# BMS_1_2026-08-27.net
KiCad netlist of a schematic drawn in Altium Designer
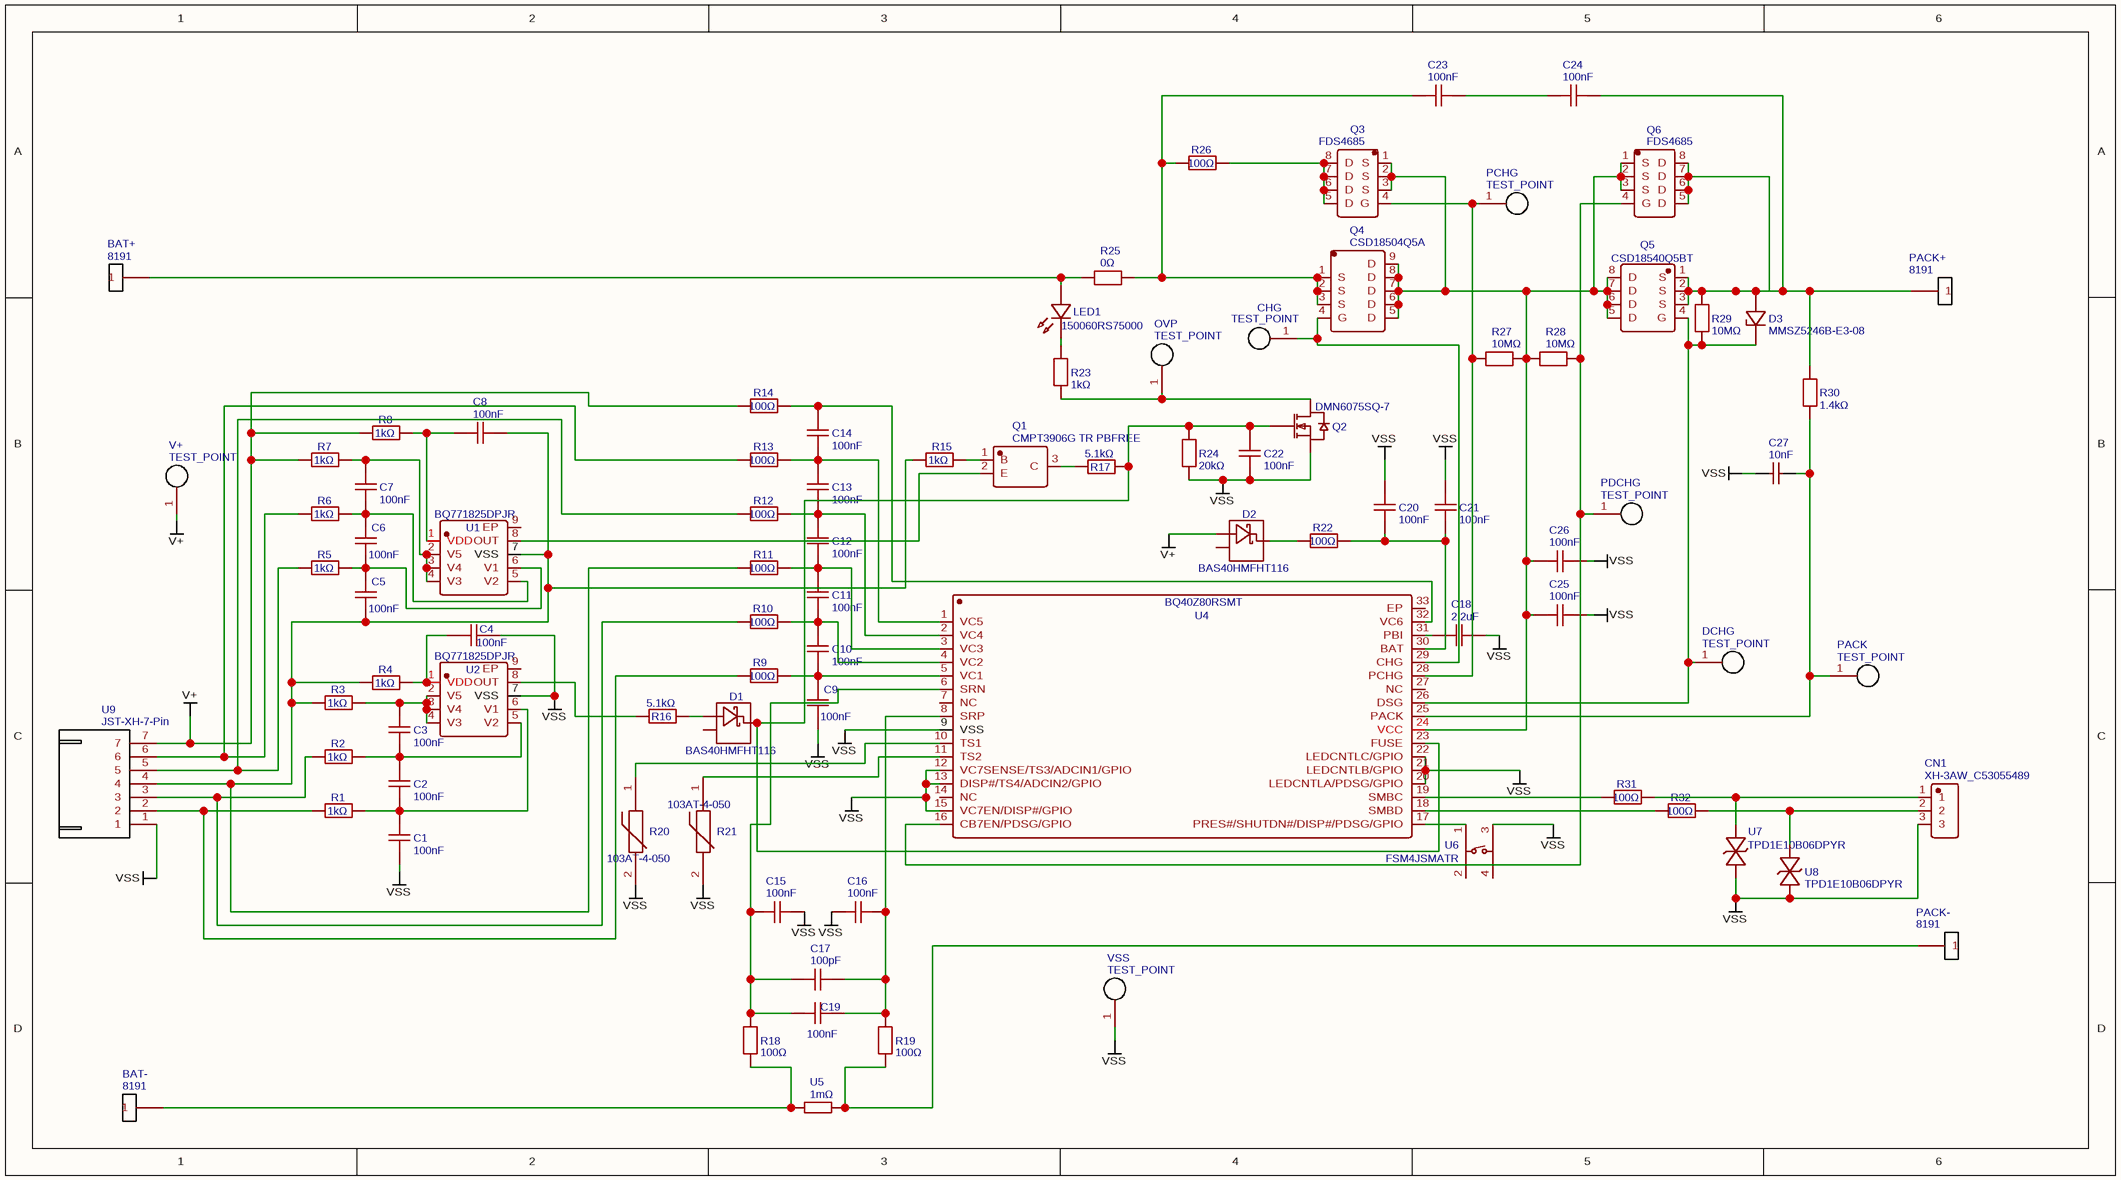
[diagram p0: BMS_1_2026-08-27.schdoc]

(export (version "E")
  (design (tool "Eeschema 10.0.6"))
  (components
    (comp (ref "BAT+")
      (value "8191")
      (fields (field (name "CONTRIBUTOR") "carlo1300"))
      (libsource (lib "altium-import") (part "root_0_8191_"))
    )
    (comp (ref "BAT-")
      (value "8191")
      (fields (field (name "CONTRIBUTOR") "carlo1300"))
      (libsource (lib "altium-import") (part "root_0_8191_"))
    )
    (comp (ref "C1")
      (value "100nF")
      (fields
        (field (name "MANUFACTURER") "muRata(村田)")
        (field (name "MANUFACTURER PART") "GRM188R71H104KA93D")
      )
      (libsource (lib "altium-import") (part "root_1_100nF_"))
    )
    (comp (ref "C2")
      (value "100nF")
      (fields
        (field (name "MANUFACTURER") "muRata(村田)")
        (field (name "MANUFACTURER PART") "GRM188R71H104KA93D")
      )
      (libsource (lib "altium-import") (part "root_1_100nF_"))
    )
    (comp (ref "C3")
      (value "100nF")
      (fields
        (field (name "MANUFACTURER") "muRata(村田)")
        (field (name "MANUFACTURER PART") "GRM188R71H104KA93D")
      )
      (libsource (lib "altium-import") (part "root_1_100nF_"))
    )
    (comp (ref "C4")
      (value "100nF")
      (fields
        (field (name "MANUFACTURER") "muRata(村田)")
        (field (name "MANUFACTURER PART") "GRM188R71H104KA93D")
      )
      (libsource (lib "altium-import") (part "root_2_100nF_"))
    )
    (comp (ref "C5")
      (value "100nF")
      (fields
        (field (name "MANUFACTURER") "muRata(村田)")
        (field (name "MANUFACTURER PART") "GRM188R71H104KA93D")
      )
      (libsource (lib "altium-import") (part "root_1_100nF_"))
    )
    (comp (ref "C6")
      (value "100nF")
      (fields
        (field (name "MANUFACTURER") "muRata(村田)")
        (field (name "MANUFACTURER PART") "GRM188R71H104KA93D")
      )
      (libsource (lib "altium-import") (part "root_1_100nF_"))
    )
    (comp (ref "C7")
      (value "100nF")
      (fields
        (field (name "MANUFACTURER") "muRata(村田)")
        (field (name "MANUFACTURER PART") "GRM188R71H104KA93D")
      )
      (libsource (lib "altium-import") (part "root_1_100nF_"))
    )
    (comp (ref "C8")
      (value "100nF")
      (fields
        (field (name "MANUFACTURER") "muRata(村田)")
        (field (name "MANUFACTURER PART") "GRM188R71H104KA93D")
      )
      (libsource (lib "altium-import") (part "root_2_100nF_"))
    )
    (comp (ref "C9")
      (value "100nF")
      (fields
        (field (name "MANUFACTURER") "muRata(村田)")
        (field (name "MANUFACTURER PART") "GRM188R71H104KA93D")
      )
      (libsource (lib "altium-import") (part "root_1_100nF_"))
    )
    (comp (ref "C10")
      (value "100nF")
      (fields
        (field (name "MANUFACTURER") "muRata(村田)")
        (field (name "MANUFACTURER PART") "GRM188R71H104KA93D")
      )
      (libsource (lib "altium-import") (part "root_1_100nF_"))
    )
    (comp (ref "C11")
      (value "100nF")
      (fields
        (field (name "MANUFACTURER") "muRata(村田)")
        (field (name "MANUFACTURER PART") "GRM188R71H104KA93D")
      )
      (libsource (lib "altium-import") (part "root_1_100nF_"))
    )
    (comp (ref "C12")
      (value "100nF")
      (fields
        (field (name "MANUFACTURER") "muRata(村田)")
        (field (name "MANUFACTURER PART") "GRM188R71H104KA93D")
      )
      (libsource (lib "altium-import") (part "root_1_100nF_"))
    )
    (comp (ref "C13")
      (value "100nF")
      (fields
        (field (name "MANUFACTURER") "muRata(村田)")
        (field (name "MANUFACTURER PART") "GRM188R71H104KA93D")
      )
      (libsource (lib "altium-import") (part "root_1_100nF_"))
    )
    (comp (ref "C14")
      (value "100nF")
      (fields
        (field (name "MANUFACTURER") "muRata(村田)")
        (field (name "MANUFACTURER PART") "GRM188R71H104KA93D")
      )
      (libsource (lib "altium-import") (part "root_1_100nF_"))
    )
    (comp (ref "C15")
      (value "100nF")
      (fields
        (field (name "MANUFACTURER") "muRata(村田)")
        (field (name "MANUFACTURER PART") "GRM188R71H104KA93D")
      )
      (libsource (lib "altium-import") (part "root_0_100nF_"))
    )
    (comp (ref "C16")
      (value "100nF")
      (fields
        (field (name "MANUFACTURER") "muRata(村田)")
        (field (name "MANUFACTURER PART") "GRM188R71H104KA93D")
      )
      (libsource (lib "altium-import") (part "root_2_100nF_"))
    )
    (comp (ref "C17")
      (value "100pF")
      (fields
        (field (name "MANUFACTURER") "KEMET(基美)")
        (field (name "MANUFACTURER PART") "C0603C101J5GAC3121")
        (field (name "CONTRIBUTOR") "LCSC")
      )
      (libsource (lib "altium-import") (part "root_0_100pF_"))
    )
    (comp (ref "C18")
      (value "2.2uF")
      (fields
        (field (name "MANUFACTURER") "muRata(村田)")
        (field (name "MANUFACTURER PART") "GRM21BR71E225KA73L")
        (field (name "CONTRIBUTOR") "LCSC")
      )
      (libsource (lib "altium-import") (part "root_0_2.2uF_"))
    )
    (comp (ref "C19")
      (value "100nF")
      (fields
        (field (name "MANUFACTURER") "muRata(村田)")
        (field (name "MANUFACTURER PART") "GRM188R71H104KA93D")
      )
      (libsource (lib "altium-import") (part "root_2_100nF_"))
    )
    (comp (ref "C20")
      (value "100nF")
      (fields
        (field (name "MANUFACTURER") "muRata(村田)")
        (field (name "MANUFACTURER PART") "GRM188R71H104KA93D")
      )
      (libsource (lib "altium-import") (part "root_1_100nF_"))
    )
    (comp (ref "C21")
      (value "100nF")
      (fields
        (field (name "MANUFACTURER") "muRata(村田)")
        (field (name "MANUFACTURER PART") "GRM188R71H104KA93D")
      )
      (libsource (lib "altium-import") (part "root_1_100nF_"))
    )
    (comp (ref "C22")
      (value "100nF")
      (fields
        (field (name "MANUFACTURER") "muRata(村田)")
        (field (name "MANUFACTURER PART") "GRM188R71H104KA93D")
      )
      (libsource (lib "altium-import") (part "root_1_100nF_"))
    )
    (comp (ref "C23")
      (value "100nF")
      (fields
        (field (name "MANUFACTURER") "muRata(村田)")
        (field (name "MANUFACTURER PART") "GRM188R71H104KA93D")
      )
      (libsource (lib "altium-import") (part "root_2_100nF_"))
    )
    (comp (ref "C24")
      (value "100nF")
      (fields
        (field (name "MANUFACTURER") "muRata(村田)")
        (field (name "MANUFACTURER PART") "GRM188R71H104KA93D")
      )
      (libsource (lib "altium-import") (part "root_2_100nF_"))
    )
    (comp (ref "C25")
      (value "100nF")
      (fields
        (field (name "MANUFACTURER") "muRata(村田)")
        (field (name "MANUFACTURER PART") "GRM188R71H104KA93D")
      )
      (libsource (lib "altium-import") (part "root_2_100nF_"))
    )
    (comp (ref "C26")
      (value "100nF")
      (fields
        (field (name "MANUFACTURER") "muRata(村田)")
        (field (name "MANUFACTURER PART") "GRM188R71H104KA93D")
      )
      (libsource (lib "altium-import") (part "root_2_100nF_"))
    )
    (comp (ref "C27")
      (value "10nF")
      (fields
        (field (name "MANUFACTURER PART") "GRM188R71H103KA01D")
        (field (name "MANUFACTURER") "muRata(村田)")
      )
      (libsource (lib "altium-import") (part "root_0_10nF_"))
    )
    (comp (ref "CHG")
      (value "TEST_POINT")
      (fields (field (name "CONTRIBUTOR") "erandi"))
      (libsource (lib "altium-import") (part "root_0_TEST_POINT_"))
    )
    (comp (ref "CN1")
      (value "XH-3AW_C53055489")
      (fields
        (field (name "MANUFACTURER") "LXWCONN(连兴旺电子)")
        (field (name "MANUFACTURER PART") "XH-3AW")
        (field (name "CONTRIBUTOR") "lcsc")
      )
      (libsource (lib "altium-import") (part "root_0_XH-3AW_C53055489_"))
    )
    (comp (ref "D1")
      (value "BAS40HMFHT116")
      (fields (field (name "MANUFACTURER") "ROHM(罗姆)") (field (name "CONTRIBUTOR") "LCSC"))
      (libsource (lib "altium-import") (part "root_3_BAS40HMFHT116_"))
    )
    (comp (ref "D2")
      (value "BAS40HMFHT116")
      (fields (field (name "MANUFACTURER") "ROHM(罗姆)") (field (name "CONTRIBUTOR") "LCSC"))
      (libsource (lib "altium-import") (part "root_3_BAS40HMFHT116_"))
    )
    (comp (ref "D3")
      (value "MMSZ5246B-E3-08")
      (fields (field (name "MANUFACTURER") "VISHAY(威世)") (field (name "CONTRIBUTOR") "lcsc"))
      (libsource (lib "altium-import") (part "root_3_MMSZ5246B-E3-08_"))
    )
    (comp (ref "DCHG")
      (value "TEST_POINT")
      (fields (field (name "CONTRIBUTOR") "erandi"))
      (libsource (lib "altium-import") (part "root_2_TEST_POINT_"))
    )
    (comp (ref "LED1")
      (value "150060RS75000")
      (fields (field (name "MANUFACTURER") "Wurth(伍尔特)") (field (name "CONTRIBUTOR") "lcsc"))
      (libsource (lib "altium-import") (part "root_1_150060RS75000_"))
    )
    (comp (ref "OVP")
      (value "TEST_POINT")
      (fields (field (name "CONTRIBUTOR") "erandi"))
      (libsource (lib "altium-import") (part "root_3_TEST_POINT_"))
    )
    (comp (ref "PACK")
      (value "TEST_POINT")
      (fields (field (name "CONTRIBUTOR") "erandi"))
      (libsource (lib "altium-import") (part "root_2_TEST_POINT_"))
    )
    (comp (ref "PACK+")
      (value "8191")
      (fields (field (name "CONTRIBUTOR") "carlo1300"))
      (libsource (lib "altium-import") (part "root_2_8191_"))
    )
    (comp (ref "PACK-")
      (value "8191")
      (fields (field (name "CONTRIBUTOR") "carlo1300"))
      (libsource (lib "altium-import") (part "root_2_8191_"))
    )
    (comp (ref "PCHG")
      (value "TEST_POINT")
      (fields (field (name "CONTRIBUTOR") "erandi"))
      (libsource (lib "altium-import") (part "root_2_TEST_POINT_"))
    )
    (comp (ref "PDCHG")
      (value "TEST_POINT")
      (fields (field (name "CONTRIBUTOR") "erandi"))
      (libsource (lib "altium-import") (part "root_2_TEST_POINT_"))
    )
    (comp (ref "Q1")
      (value "CMPT3906G TR PBFREE")
      (fields (field (name "MANUFACTURER") "Central(中环)") (field (name "CONTRIBUTOR") "lcsc"))
      (libsource (lib "altium-import") (part "root_0_CMPT3906G TR PBFREE_"))
    )
    (comp (ref "Q2")
      (value "DMN6075SQ-7")
      (fields (field (name "MANUFACTURER") "DIODES(美台)") (field (name "CONTRIBUTOR") "lcsc"))
      (libsource (lib "altium-import") (part "root_0_DMN6075SQ-7_"))
    )
    (comp (ref "Q3")
      (value "FDS4685")
      (fields (field (name "MANUFACTURER") "onsemi(安森美)") (field (name "CONTRIBUTOR") "LCSC"))
      (libsource (lib "") (part "root_0_FDS4685__1"))
    )
    (comp (ref "Q4")
      (value "CSD18504Q5A")
      (fields (field (name "MANUFACTURER") "TI(德州仪器)") (field (name "CONTRIBUTOR") "LCSC"))
      (libsource (lib "altium-import") (part "root_0_CSD18504Q5A_"))
    )
    (comp (ref "Q5")
      (value "CSD18540Q5BT")
      (fields (field (name "MANUFACTURER") "TI(德州仪器)") (field (name "CONTRIBUTOR") "LCSC"))
      (libsource (lib "altium-import") (part "root_0_CSD18540Q5BT_"))
    )
    (comp (ref "Q6")
      (value "FDS4685")
      (fields (field (name "MANUFACTURER") "onsemi(安森美)") (field (name "CONTRIBUTOR") "LCSC"))
      (libsource (lib "altium-import") (part "root_0_FDS4685_"))
    )
    (comp (ref "R1")
      (value "1kΩ")
      (fields
        (field (name "MANUFACTURER") "VISHAY(威世)")
        (field (name "MANUFACTURER PART") "CRCW06031K00JNEA")
        (field (name "CONTRIBUTOR") "LCSC")
      )
      (libsource (lib "altium-import") (part "root_0_1kΩ_"))
    )
    (comp (ref "R2")
      (value "1kΩ")
      (fields
        (field (name "MANUFACTURER") "VISHAY(威世)")
        (field (name "MANUFACTURER PART") "CRCW06031K00JNEA")
        (field (name "CONTRIBUTOR") "LCSC")
      )
      (libsource (lib "altium-import") (part "root_0_1kΩ_"))
    )
    (comp (ref "R3")
      (value "1kΩ")
      (fields
        (field (name "MANUFACTURER") "VISHAY(威世)")
        (field (name "MANUFACTURER PART") "CRCW06031K00JNEA")
        (field (name "CONTRIBUTOR") "LCSC")
      )
      (libsource (lib "altium-import") (part "root_0_1kΩ_"))
    )
    (comp (ref "R4")
      (value "1kΩ")
      (fields
        (field (name "MANUFACTURER") "VISHAY(威世)")
        (field (name "MANUFACTURER PART") "CRCW06031K00JNEA")
        (field (name "CONTRIBUTOR") "LCSC")
      )
      (libsource (lib "altium-import") (part "root_0_1kΩ_"))
    )
    (comp (ref "R5")
      (value "1kΩ")
      (fields
        (field (name "MANUFACTURER") "VISHAY(威世)")
        (field (name "MANUFACTURER PART") "CRCW06031K00JNEA")
        (field (name "CONTRIBUTOR") "LCSC")
      )
      (libsource (lib "altium-import") (part "root_0_1kΩ_"))
    )
    (comp (ref "R6")
      (value "1kΩ")
      (fields
        (field (name "MANUFACTURER") "VISHAY(威世)")
        (field (name "MANUFACTURER PART") "CRCW06031K00JNEA")
        (field (name "CONTRIBUTOR") "LCSC")
      )
      (libsource (lib "altium-import") (part "root_0_1kΩ_"))
    )
    (comp (ref "R7")
      (value "1kΩ")
      (fields
        (field (name "MANUFACTURER") "VISHAY(威世)")
        (field (name "MANUFACTURER PART") "CRCW06031K00JNEA")
        (field (name "CONTRIBUTOR") "LCSC")
      )
      (libsource (lib "altium-import") (part "root_0_1kΩ_"))
    )
    (comp (ref "R8")
      (value "1kΩ")
      (fields
        (field (name "MANUFACTURER") "VISHAY(威世)")
        (field (name "MANUFACTURER PART") "CRCW06031K00JNEA")
        (field (name "CONTRIBUTOR") "LCSC")
      )
      (libsource (lib "altium-import") (part "root_0_1kΩ_"))
    )
    (comp (ref "R9")
      (value "100Ω")
      (fields
        (field (name "MANUFACTURER") "VISHAY(威世)")
        (field (name "MANUFACTURER PART") "CRCW0603100RJNEA")
        (field (name "CONTRIBUTOR") "LCSC")
      )
      (libsource (lib "altium-import") (part "root_0_100Ω_"))
    )
    (comp (ref "R10")
      (value "100Ω")
      (fields
        (field (name "MANUFACTURER") "VISHAY(威世)")
        (field (name "MANUFACTURER PART") "CRCW0603100RJNEA")
        (field (name "CONTRIBUTOR") "LCSC")
      )
      (libsource (lib "altium-import") (part "root_0_100Ω_"))
    )
    (comp (ref "R11")
      (value "100Ω")
      (fields
        (field (name "MANUFACTURER") "VISHAY(威世)")
        (field (name "MANUFACTURER PART") "CRCW0603100RJNEA")
        (field (name "CONTRIBUTOR") "LCSC")
      )
      (libsource (lib "altium-import") (part "root_0_100Ω_"))
    )
    (comp (ref "R12")
      (value "100Ω")
      (fields
        (field (name "MANUFACTURER") "VISHAY(威世)")
        (field (name "MANUFACTURER PART") "CRCW0603100RJNEA")
        (field (name "CONTRIBUTOR") "LCSC")
      )
      (libsource (lib "altium-import") (part "root_0_100Ω_"))
    )
    (comp (ref "R13")
      (value "100Ω")
      (fields
        (field (name "MANUFACTURER") "VISHAY(威世)")
        (field (name "MANUFACTURER PART") "CRCW0603100RJNEA")
        (field (name "CONTRIBUTOR") "LCSC")
      )
      (libsource (lib "altium-import") (part "root_0_100Ω_"))
    )
    (comp (ref "R14")
      (value "100Ω")
      (fields
        (field (name "MANUFACTURER") "VISHAY(威世)")
        (field (name "MANUFACTURER PART") "CRCW0603100RJNEA")
        (field (name "CONTRIBUTOR") "LCSC")
      )
      (libsource (lib "altium-import") (part "root_0_100Ω_"))
    )
    (comp (ref "R15")
      (value "1kΩ")
      (fields
        (field (name "MANUFACTURER") "VISHAY(威世)")
        (field (name "MANUFACTURER PART") "CRCW06031K00JNEA")
        (field (name "CONTRIBUTOR") "LCSC")
      )
      (libsource (lib "altium-import") (part "root_0_1kΩ_"))
    )
    (comp (ref "R16")
      (value "5.1kΩ")
      (fields
        (field (name "MANUFACTURER") "VISHAY(威世)")
        (field (name "MANUFACTURER PART") "CRCW06035K10JNEA")
        (field (name "CONTRIBUTOR") "LCSC")
      )
      (libsource (lib "altium-import") (part "root_0_5.1kΩ_"))
    )
    (comp (ref "R17")
      (value "5.1kΩ")
      (fields
        (field (name "MANUFACTURER") "VISHAY(威世)")
        (field (name "MANUFACTURER PART") "CRCW06035K10JNEA")
        (field (name "CONTRIBUTOR") "LCSC")
      )
      (libsource (lib "altium-import") (part "root_0_5.1kΩ_"))
    )
    (comp (ref "R18")
      (value "100Ω")
      (fields
        (field (name "MANUFACTURER") "VISHAY(威世)")
        (field (name "MANUFACTURER PART") "CRCW0603100RJNEA")
        (field (name "CONTRIBUTOR") "LCSC")
      )
      (libsource (lib "altium-import") (part "root_3_100Ω_"))
    )
    (comp (ref "R19")
      (value "100Ω")
      (fields
        (field (name "MANUFACTURER") "VISHAY(威世)")
        (field (name "MANUFACTURER PART") "CRCW0603100RJNEA")
        (field (name "CONTRIBUTOR") "LCSC")
      )
      (libsource (lib "altium-import") (part "root_1_100Ω_"))
    )
    (comp (ref "R20")
      (value "103AT-4-050")
      (fields (field (name "MANUFACTURER") "semitec(石冢)") (field (name "CONTRIBUTOR") "LCSC"))
      (libsource (lib "altium-import") (part "root_3_103AT-4-050_"))
    )
    (comp (ref "R21")
      (value "103AT-4-050")
      (fields (field (name "MANUFACTURER") "semitec(石冢)") (field (name "CONTRIBUTOR") "LCSC"))
      (libsource (lib "altium-import") (part "root_3_103AT-4-050_"))
    )
    (comp (ref "R22")
      (value "100Ω")
      (fields
        (field (name "MANUFACTURER") "VISHAY(威世)")
        (field (name "MANUFACTURER PART") "CRCW0603100RJNEA")
        (field (name "CONTRIBUTOR") "LCSC")
      )
      (libsource (lib "altium-import") (part "root_0_100Ω_"))
    )
    (comp (ref "R23")
      (value "1kΩ")
      (fields
        (field (name "MANUFACTURER") "VISHAY(威世)")
        (field (name "MANUFACTURER PART") "CRCW06031K00JNEA")
        (field (name "CONTRIBUTOR") "LCSC")
      )
      (libsource (lib "altium-import") (part "root_1_1kΩ_"))
    )
    (comp (ref "R24")
      (value "20kΩ")
      (fields
        (field (name "MANUFACTURER") "VISHAY(威世)")
        (field (name "MANUFACTURER PART") "CRCW060320K0JNEA")
        (field (name "CONTRIBUTOR") "LCSC")
      )
      (libsource (lib "altium-import") (part "root_1_20kΩ_"))
    )
    (comp (ref "R25")
      (value "0Ω")
      (fields
        (field (name "MANUFACTURER") "VISHAY(威世)")
        (field (name "MANUFACTURER PART") "RCL12250000Z0EG")
        (field (name "CONTRIBUTOR") "lcsc")
      )
      (libsource (lib "altium-import") (part "root_0_0Ω_"))
    )
    (comp (ref "R26")
      (value "100Ω")
      (fields
        (field (name "MANUFACTURER") "VISHAY(威世)")
        (field (name "MANUFACTURER PART") "CRCW0603100RJNEA")
        (field (name "CONTRIBUTOR") "LCSC")
      )
      (libsource (lib "altium-import") (part "root_0_100Ω_"))
    )
    (comp (ref "R27")
      (value "10MΩ")
      (fields
        (field (name "MANUFACTURER") "VISHAY(威世)")
        (field (name "MANUFACTURER PART") "CRCW060310M0JNEA")
        (field (name "CONTRIBUTOR") "lcsc")
      )
      (libsource (lib "altium-import") (part "root_0_10MΩ_"))
    )
    (comp (ref "R28")
      (value "10MΩ")
      (fields
        (field (name "MANUFACTURER") "VISHAY(威世)")
        (field (name "MANUFACTURER PART") "CRCW060310M0JNEA")
        (field (name "CONTRIBUTOR") "lcsc")
      )
      (libsource (lib "altium-import") (part "root_0_10MΩ_"))
    )
    (comp (ref "R29")
      (value "10MΩ")
      (fields
        (field (name "MANUFACTURER") "VISHAY(威世)")
        (field (name "MANUFACTURER PART") "CRCW060310M0JNEA")
        (field (name "CONTRIBUTOR") "lcsc")
      )
      (libsource (lib "altium-import") (part "root_1_10MΩ_"))
    )
    (comp (ref "R30")
      (value "1.4kΩ")
      (fields
        (field (name "MANUFACTURER") "VISHAY(威世)")
        (field (name "MANUFACTURER PART") "CRCW06031K40FKEA")
        (field (name "CONTRIBUTOR") "LCSC")
      )
      (libsource (lib "altium-import") (part "root_1_1.4kΩ_"))
    )
    (comp (ref "R31")
      (value "100Ω")
      (fields
        (field (name "MANUFACTURER") "VISHAY(威世)")
        (field (name "MANUFACTURER PART") "CRCW0603100RJNEA")
        (field (name "CONTRIBUTOR") "LCSC")
      )
      (libsource (lib "altium-import") (part "root_0_100Ω_"))
    )
    (comp (ref "R32")
      (value "100Ω")
      (fields
        (field (name "MANUFACTURER") "VISHAY(威世)")
        (field (name "MANUFACTURER PART") "CRCW0603100RJNEA")
        (field (name "CONTRIBUTOR") "LCSC")
      )
      (libsource (lib "altium-import") (part "root_0_100Ω_"))
    )
    (comp (ref "U1")
      (value "BQ771825DPJR")
      (fields (field (name "MANUFACTURER") "TI(德州仪器)") (field (name "CONTRIBUTOR") "lcsc"))
      (libsource (lib "altium-import") (part "root_0_BQ771825DPJR_"))
    )
    (comp (ref "U2")
      (value "BQ771825DPJR")
      (fields (field (name "MANUFACTURER") "TI(德州仪器)") (field (name "CONTRIBUTOR") "lcsc"))
      (libsource (lib "altium-import") (part "root_0_BQ771825DPJR_"))
    )
    (comp (ref "U4")
      (value "BQ40Z80RSMT")
      (fields (field (name "MANUFACTURER") "TI(德州仪器)") (field (name "CONTRIBUTOR") "lcsc"))
      (libsource (lib "altium-import") (part "root_0_BQ40Z80RSMT_"))
    )
    (comp (ref "U5")
      (value "1mΩ")
      (fields
        (field (name "MANUFACTURER") "ROHM(罗姆)")
        (field (name "MANUFACTURER PART") "PMR25HZPFV1L00")
        (field (name "CONTRIBUTOR") "LCSC")
      )
      (libsource (lib "altium-import") (part "root_2_1mΩ_"))
    )
    (comp (ref "U6")
      (value "FSM4JSMATR")
      (fields (field (name "MANUFACTURER") "TE Connectivity(泰科电子)") (field (name "CONTRIBUTOR") "lcsc"))
      (libsource (lib "altium-import") (part "root_1_FSM4JSMATR_"))
    )
    (comp (ref "U7")
      (value "TPD1E10B06DPYR")
      (fields (field (name "MANUFACTURER") "TI(德州仪器)") (field (name "CONTRIBUTOR") "LCSC"))
      (libsource (lib "altium-import") (part "root_3_TPD1E10B06DPYR_"))
    )
    (comp (ref "U8")
      (value "TPD1E10B06DPYR")
      (fields (field (name "MANUFACTURER") "TI(德州仪器)") (field (name "CONTRIBUTOR") "LCSC"))
      (libsource (lib "altium-import") (part "root_3_TPD1E10B06DPYR_"))
    )
    (comp (ref "U9")
      (value "JST-XH-7-Pin")
      (fields (field (name "CONTRIBUTOR") "loyboy"))
      (libsource (lib "altium-import") (part "root_2_JST-XH-7-Pin_"))
    )
    (comp (ref "V+")
      (value "TEST_POINT")
      (fields (field (name "CONTRIBUTOR") "erandi"))
      (libsource (lib "altium-import") (part "root_3_TEST_POINT_"))
    )
    (comp (ref "VSS")
      (value "TEST_POINT")
      (fields (field (name "CONTRIBUTOR") "erandi"))
      (libsource (lib "altium-import") (part "root_3_TEST_POINT_"))
    )
  )
  (nets
    (net (code "1") (name "Net-(BAT--Pad1)") (class "Default")
      (node (ref "BAT-") (pin "1") (pinfunction "1_1") (pintype "passive"))
      (node (ref "R18") (pin "2") (pinfunction "2_2") (pintype "passive"))
      (node (ref "U5") (pin "2") (pinfunction "2_2") (pintype "passive"))
    )
    (net (code "2") (name "Net-(C23-Pad1)") (class "Default")
      (node (ref "C23") (pin "1") (pinfunction "1_1") (pintype "passive"))
      (node (ref "C24") (pin "2") (pinfunction "2_2") (pintype "passive"))
    )
    (net (code "3") (name "Net-(C23-Pad2)") (class "Default")
      (node (ref "C23") (pin "2") (pinfunction "2_2") (pintype "passive"))
      (node (ref "Q4") (pin "1") (pinfunction "S_1") (pintype "passive"))
      (node (ref "Q4") (pin "2") (pinfunction "S_2") (pintype "passive"))
      (node (ref "Q4") (pin "3") (pinfunction "S_3") (pintype "passive"))
      (node (ref "R25") (pin "2") (pinfunction "2_2") (pintype "passive"))
      (node (ref "R26") (pin "1") (pinfunction "1_1") (pintype "passive"))
    )
    (net (code "4") (name "Net-(CHG-TEST)") (class "Default")
      (node (ref "CHG") (pin "1") (pinfunction "TEST_1") (pintype "passive"))
      (node (ref "Q4") (pin "4") (pinfunction "G_4") (pintype "passive"))
      (node (ref "U4") (pin "29") (pinfunction "CHG_29") (pintype "passive"))
    )
    (net (code "5") (name "Net-(CN1-Pad1)") (class "Default")
      (node (ref "CN1") (pin "1") (pinfunction "1_1") (pintype "passive"))
      (node (ref "R31") (pin "2") (pinfunction "2_2") (pintype "passive"))
      (node (ref "U7") (pin "1") (pinfunction "1_1") (pintype "passive"))
    )
    (net (code "6") (name "Net-(CN1-Pad2)") (class "Default")
      (node (ref "CN1") (pin "2") (pinfunction "2_2") (pintype "passive"))
      (node (ref "R32") (pin "2") (pinfunction "2_2") (pintype "passive"))
      (node (ref "U8") (pin "1") (pinfunction "1_1") (pintype "passive"))
    )
    (net (code "7") (name "Net-(D1-A)") (class "Default")
      (node (ref "D1") (pin "1") (pinfunction "A_1") (pintype "passive"))
      (node (ref "R16") (pin "2") (pinfunction "2_2") (pintype "passive"))
    )
    (net (code "8") (name "Net-(D1-K)") (class "Default")
      (node (ref "C22") (pin "2") (pinfunction "2_2") (pintype "passive"))
      (node (ref "D1") (pin "3") (pinfunction "K_3") (pintype "passive"))
      (node (ref "Q2") (pin "1") (pinfunction "G_1") (pintype "passive"))
      (node (ref "R17") (pin "2") (pinfunction "2_2") (pintype "passive"))
      (node (ref "R24") (pin "2") (pinfunction "2_2") (pintype "passive"))
      (node (ref "U4") (pin "23") (pinfunction "FUSE_23") (pintype "passive"))
    )
    (net (code "9") (name "Net-(D2-K)") (class "Default")
      (node (ref "D2") (pin "3") (pinfunction "K_3") (pintype "passive"))
      (node (ref "R22") (pin "1") (pinfunction "1_1") (pintype "passive"))
    )
    (net (code "10") (name "Net-(D3-A)") (class "Default")
      (node (ref "C24") (pin "1") (pinfunction "1_1") (pintype "passive"))
      (node (ref "D3") (pin "1") (pinfunction "A_1") (pintype "passive"))
      (node (ref "PACK+") (pin "1") (pinfunction "1_1") (pintype "passive"))
      (node (ref "Q5") (pin "1") (pinfunction "S_1") (pintype "passive"))
      (node (ref "Q5") (pin "2") (pinfunction "S_2") (pintype "passive"))
      (node (ref "Q5") (pin "3") (pinfunction "S_3") (pintype "passive"))
      (node (ref "Q6") (pin "5") (pinfunction "D_5") (pintype "passive"))
      (node (ref "Q6") (pin "6") (pinfunction "D_6") (pintype "passive"))
      (node (ref "Q6") (pin "7") (pinfunction "D_7") (pintype "passive"))
      (node (ref "Q6") (pin "8") (pinfunction "D_8") (pintype "passive"))
      (node (ref "R29") (pin "2") (pinfunction "2_2") (pintype "passive"))
      (node (ref "R30") (pin "2") (pinfunction "2_2") (pintype "passive"))
    )
    (net (code "11") (name "Net-(D3-C)") (class "Default")
      (node (ref "D3") (pin "2") (pinfunction "C_2") (pintype "passive"))
      (node (ref "DCHG") (pin "1") (pinfunction "TEST_1") (pintype "passive"))
      (node (ref "Q5") (pin "4") (pinfunction "G_4") (pintype "passive"))
      (node (ref "R29") (pin "1") (pinfunction "1_1") (pintype "passive"))
      (node (ref "U4") (pin "26") (pinfunction "DSG_26") (pintype "passive"))
    )
    (net (code "12") (name "Net-(LED1-A)") (class "Default")
      (node (ref "BAT+") (pin "1") (pinfunction "1_1") (pintype "passive"))
      (node (ref "LED1") (pin "2") (pinfunction "A_2") (pintype "passive"))
      (node (ref "R25") (pin "1") (pinfunction "1_1") (pintype "passive"))
    )
    (net (code "13") (name "Net-(LED1-K)") (class "Default")
      (node (ref "LED1") (pin "1") (pinfunction "K_1") (pintype "passive"))
      (node (ref "R23") (pin "2") (pinfunction "2_2") (pintype "passive"))
    )
    (net (code "14") (name "Net-(OVP-TEST)") (class "Default")
      (node (ref "OVP") (pin "1") (pinfunction "TEST_1") (pintype "passive"))
      (node (ref "Q2") (pin "3") (pinfunction "D_3") (pintype "passive"))
      (node (ref "R23") (pin "1") (pinfunction "1_1") (pintype "passive"))
    )
    (net (code "15") (name "Net-(PACK--Pad1)") (class "Default")
      (node (ref "PACK-") (pin "1") (pinfunction "1_1") (pintype "passive"))
      (node (ref "R19") (pin "1") (pinfunction "1_1") (pintype "passive"))
      (node (ref "U5") (pin "1") (pinfunction "1_1") (pintype "passive"))
    )
    (net (code "16") (name "Net-(PACK-TEST)") (class "Default")
      (node (ref "C27") (pin "2") (pinfunction "2_2") (pintype "passive"))
      (node (ref "PACK") (pin "1") (pinfunction "TEST_1") (pintype "passive"))
      (node (ref "R30") (pin "1") (pinfunction "1_1") (pintype "passive"))
      (node (ref "U4") (pin "25") (pinfunction "PACK_25") (pintype "passive"))
    )
    (net (code "17") (name "Net-(PCHG-TEST)") (class "Default")
      (node (ref "PCHG") (pin "1") (pinfunction "TEST_1") (pintype "passive"))
      (node (ref "Q3") (pin "4") (pinfunction "G_4") (pintype "passive"))
      (node (ref "R27") (pin "1") (pinfunction "1_1") (pintype "passive"))
      (node (ref "U4") (pin "28") (pinfunction "PCHG_28") (pintype "passive"))
    )
    (net (code "18") (name "Net-(PDCHG-TEST)") (class "Default")
      (node (ref "PDCHG") (pin "1") (pinfunction "TEST_1") (pintype "passive"))
      (node (ref "Q6") (pin "4") (pinfunction "G_4") (pintype "passive"))
      (node (ref "R28") (pin "2") (pinfunction "2_2") (pintype "passive"))
      (node (ref "U4") (pin "16") (pinfunction "CB7EN/PDSG/GPIO_16") (pintype "passive"))
    )
    (net (code "19") (name "Net-(Q1-B)") (class "Default")
      (node (ref "Q1") (pin "1") (pinfunction "B_1") (pintype "passive"))
      (node (ref "R15") (pin "2") (pinfunction "2_2") (pintype "passive"))
    )
    (net (code "20") (name "Net-(Q1-C)") (class "Default")
      (node (ref "Q1") (pin "3") (pinfunction "C_3") (pintype "passive"))
      (node (ref "R17") (pin "1") (pinfunction "1_1") (pintype "passive"))
    )
    (net (code "21") (name "Net-(Q1-E)") (class "Default")
      (node (ref "Q1") (pin "2") (pinfunction "E_2") (pintype "passive"))
      (node (ref "U1") (pin "8") (pinfunction "OUT_8") (pintype "passive"))
    )
    (net (code "22") (name "Net-(Q3-D-Pad5)") (class "Default")
      (node (ref "Q3") (pin "5") (pinfunction "D_5") (pintype "passive"))
      (node (ref "Q3") (pin "6") (pinfunction "D_6") (pintype "passive"))
      (node (ref "Q3") (pin "7") (pinfunction "D_7") (pintype "passive"))
      (node (ref "Q3") (pin "8") (pinfunction "D_8") (pintype "passive"))
      (node (ref "R26") (pin "2") (pinfunction "2_2") (pintype "passive"))
    )
    (net (code "23") (name "Net-(R1-Pad1)") (class "Default")
      (node (ref "R1") (pin "1") (pinfunction "1_1") (pintype "passive"))
      (node (ref "R9") (pin "1") (pinfunction "1_1") (pintype "passive"))
      (node (ref "U9") (pin "2") (pinfunction "2_2") (pintype "passive"))
    )
    (net (code "24") (name "Net-(R10-Pad1)") (class "Default")
      (node (ref "R10") (pin "1") (pinfunction "1_1") (pintype "passive"))
      (node (ref "R2") (pin "1") (pinfunction "1_1") (pintype "passive"))
      (node (ref "U9") (pin "3") (pinfunction "3_3") (pintype "passive"))
    )
    (net (code "25") (name "Net-(R12-Pad1)") (class "Default")
      (node (ref "R12") (pin "1") (pinfunction "1_1") (pintype "passive"))
      (node (ref "R5") (pin "1") (pinfunction "1_1") (pintype "passive"))
      (node (ref "U9") (pin "5") (pinfunction "5_5") (pintype "passive"))
    )
    (net (code "26") (name "Net-(R13-Pad1)") (class "Default")
      (node (ref "R13") (pin "1") (pinfunction "1_1") (pintype "passive"))
      (node (ref "R6") (pin "1") (pinfunction "1_1") (pintype "passive"))
      (node (ref "U9") (pin "6") (pinfunction "6_6") (pintype "passive"))
    )
    (net (code "27") (name "Net-(U1-V1)") (class "Default")
      (node (ref "C5") (pin "2") (pinfunction "2_2") (pintype "passive"))
      (node (ref "C6") (pin "1") (pinfunction "1_1") (pintype "passive"))
      (node (ref "R5") (pin "2") (pinfunction "2_2") (pintype "passive"))
      (node (ref "U1") (pin "6") (pinfunction "V1_6") (pintype "passive"))
    )
    (net (code "28") (name "Net-(U1-V2)") (class "Default")
      (node (ref "C6") (pin "2") (pinfunction "2_2") (pintype "passive"))
      (node (ref "C7") (pin "1") (pinfunction "1_1") (pintype "passive"))
      (node (ref "R6") (pin "2") (pinfunction "2_2") (pintype "passive"))
      (node (ref "U1") (pin "5") (pinfunction "V2_5") (pintype "passive"))
    )
    (net (code "29") (name "Net-(U1-V3)") (class "Default")
      (node (ref "C7") (pin "2") (pinfunction "2_2") (pintype "passive"))
      (node (ref "R7") (pin "2") (pinfunction "2_2") (pintype "passive"))
      (node (ref "U1") (pin "2") (pinfunction "V5_2") (pintype "passive"))
      (node (ref "U1") (pin "3") (pinfunction "V4_3") (pintype "passive"))
      (node (ref "U1") (pin "4") (pinfunction "V3_4") (pintype "passive"))
    )
    (net (code "30") (name "Net-(U1-VDD)") (class "Default")
      (node (ref "C8") (pin "2") (pinfunction "2_2") (pintype "passive"))
      (node (ref "R8") (pin "2") (pinfunction "2_2") (pintype "passive"))
      (node (ref "U1") (pin "1") (pinfunction "VDD_1") (pintype "passive"))
    )
    (net (code "31") (name "Net-(U1-VSS)") (class "Default")
      (node (ref "C5") (pin "1") (pinfunction "1_1") (pintype "passive"))
      (node (ref "C8") (pin "1") (pinfunction "1_1") (pintype "passive"))
      (node (ref "R11") (pin "1") (pinfunction "1_1") (pintype "passive"))
      (node (ref "R15") (pin "1") (pinfunction "1_1") (pintype "passive"))
      (node (ref "R3") (pin "1") (pinfunction "1_1") (pintype "passive"))
      (node (ref "R4") (pin "1") (pinfunction "1_1") (pintype "passive"))
      (node (ref "U1") (pin "7") (pinfunction "VSS_7") (pintype "passive"))
      (node (ref "U9") (pin "4") (pinfunction "4_4") (pintype "passive"))
    )
    (net (code "32") (name "Net-(U2-OUT)") (class "Default")
      (node (ref "R16") (pin "1") (pinfunction "1_1") (pintype "passive"))
      (node (ref "U2") (pin "8") (pinfunction "OUT_8") (pintype "passive"))
    )
    (net (code "33") (name "Net-(U2-V1)") (class "Default")
      (node (ref "C1") (pin "2") (pinfunction "2_2") (pintype "passive"))
      (node (ref "C2") (pin "1") (pinfunction "1_1") (pintype "passive"))
      (node (ref "R1") (pin "2") (pinfunction "2_2") (pintype "passive"))
      (node (ref "U2") (pin "6") (pinfunction "V1_6") (pintype "passive"))
    )
    (net (code "34") (name "Net-(U2-V2)") (class "Default")
      (node (ref "C2") (pin "2") (pinfunction "2_2") (pintype "passive"))
      (node (ref "C3") (pin "1") (pinfunction "1_1") (pintype "passive"))
      (node (ref "R2") (pin "2") (pinfunction "2_2") (pintype "passive"))
      (node (ref "U2") (pin "5") (pinfunction "V2_5") (pintype "passive"))
    )
    (net (code "35") (name "Net-(U2-V3)") (class "Default")
      (node (ref "C3") (pin "2") (pinfunction "2_2") (pintype "passive"))
      (node (ref "R3") (pin "2") (pinfunction "2_2") (pintype "passive"))
      (node (ref "U2") (pin "2") (pinfunction "V5_2") (pintype "passive"))
      (node (ref "U2") (pin "3") (pinfunction "V4_3") (pintype "passive"))
      (node (ref "U2") (pin "4") (pinfunction "V3_4") (pintype "passive"))
    )
    (net (code "36") (name "Net-(U2-VDD)") (class "Default")
      (node (ref "C4") (pin "2") (pinfunction "2_2") (pintype "passive"))
      (node (ref "R4") (pin "2") (pinfunction "2_2") (pintype "passive"))
      (node (ref "U2") (pin "1") (pinfunction "VDD_1") (pintype "passive"))
    )
    (net (code "37") (name "Net-(U4-BAT)") (class "Default")
      (node (ref "C20") (pin "1") (pinfunction "1_1") (pintype "passive"))
      (node (ref "C21") (pin "1") (pinfunction "1_1") (pintype "passive"))
      (node (ref "R22") (pin "2") (pinfunction "2_2") (pintype "passive"))
      (node (ref "U4") (pin "30") (pinfunction "BAT_30") (pintype "passive"))
    )
    (net (code "38") (name "Net-(U4-PBI)") (class "Default")
      (node (ref "C18") (pin "1") (pinfunction "1_1") (pintype "passive"))
      (node (ref "U4") (pin "31") (pinfunction "PBI_31") (pintype "passive"))
    )
    (net (code "39") (name "Net-(U4-PRES#{slash}SHUTDN#{slash}DISP#{slash}PDSG{slash}GPIO)") (class "Default")
      (node (ref "U4") (pin "17") (pinfunction "PRES#/SHUTDN#/DISP#/PDSG/GPIO_17") (pintype "passive"))
      (node (ref "U6") (pin "1") (pinfunction "1_1") (pintype "passive"))
    )
    (net (code "40") (name "Net-(U4-SMBC)") (class "Default")
      (node (ref "R31") (pin "1") (pinfunction "1_1") (pintype "passive"))
      (node (ref "U4") (pin "19") (pinfunction "SMBC_19") (pintype "passive"))
    )
    (net (code "41") (name "Net-(U4-SMBD)") (class "Default")
      (node (ref "R32") (pin "1") (pinfunction "1_1") (pintype "passive"))
      (node (ref "U4") (pin "18") (pinfunction "SMBD_18") (pintype "passive"))
    )
    (net (code "42") (name "Net-(U4-SRN)") (class "Default")
      (node (ref "C15") (pin "1") (pinfunction "1_1") (pintype "passive"))
      (node (ref "C17") (pin "1") (pinfunction "1_1") (pintype "passive"))
      (node (ref "C19") (pin "2") (pinfunction "2_2") (pintype "passive"))
      (node (ref "R18") (pin "1") (pinfunction "1_1") (pintype "passive"))
      (node (ref "U4") (pin "6") (pinfunction "SRN_6") (pintype "passive"))
    )
    (net (code "43") (name "Net-(U4-SRP)") (class "Default")
      (node (ref "C16") (pin "1") (pinfunction "1_1") (pintype "passive"))
      (node (ref "C17") (pin "2") (pinfunction "2_2") (pintype "passive"))
      (node (ref "C19") (pin "1") (pinfunction "1_1") (pintype "passive"))
      (node (ref "R19") (pin "2") (pinfunction "2_2") (pintype "passive"))
      (node (ref "U4") (pin "8") (pinfunction "SRP_8") (pintype "passive"))
    )
    (net (code "44") (name "Net-(U4-TS1)") (class "Default")
      (node (ref "R20") (pin "1") (pinfunction "1_1") (pintype "passive"))
      (node (ref "U4") (pin "10") (pinfunction "TS1_10") (pintype "passive"))
    )
    (net (code "45") (name "Net-(U4-TS2)") (class "Default")
      (node (ref "R21") (pin "1") (pinfunction "1_1") (pintype "passive"))
      (node (ref "U4") (pin "11") (pinfunction "TS2_11") (pintype "passive"))
    )
    (net (code "46") (name "Net-(U4-VC1)") (class "Default")
      (node (ref "C10") (pin "1") (pinfunction "1_1") (pintype "passive"))
      (node (ref "C9") (pin "2") (pinfunction "2_2") (pintype "passive"))
      (node (ref "R9") (pin "2") (pinfunction "2_2") (pintype "passive"))
      (node (ref "U4") (pin "5") (pinfunction "VC1_5") (pintype "passive"))
    )
    (net (code "47") (name "Net-(U4-VC2)") (class "Default")
      (node (ref "C10") (pin "2") (pinfunction "2_2") (pintype "passive"))
      (node (ref "C11") (pin "1") (pinfunction "1_1") (pintype "passive"))
      (node (ref "R10") (pin "2") (pinfunction "2_2") (pintype "passive"))
      (node (ref "U4") (pin "4") (pinfunction "VC2_4") (pintype "passive"))
    )
    (net (code "48") (name "Net-(U4-VC3)") (class "Default")
      (node (ref "C11") (pin "2") (pinfunction "2_2") (pintype "passive"))
      (node (ref "C12") (pin "1") (pinfunction "1_1") (pintype "passive"))
      (node (ref "R11") (pin "2") (pinfunction "2_2") (pintype "passive"))
      (node (ref "U4") (pin "3") (pinfunction "VC3_3") (pintype "passive"))
    )
    (net (code "49") (name "Net-(U4-VC4)") (class "Default")
      (node (ref "C12") (pin "2") (pinfunction "2_2") (pintype "passive"))
      (node (ref "C13") (pin "1") (pinfunction "1_1") (pintype "passive"))
      (node (ref "R12") (pin "2") (pinfunction "2_2") (pintype "passive"))
      (node (ref "U4") (pin "2") (pinfunction "VC4_2") (pintype "passive"))
    )
    (net (code "50") (name "Net-(U4-VC5)") (class "Default")
      (node (ref "C13") (pin "2") (pinfunction "2_2") (pintype "passive"))
      (node (ref "C14") (pin "1") (pinfunction "1_1") (pintype "passive"))
      (node (ref "R13") (pin "2") (pinfunction "2_2") (pintype "passive"))
      (node (ref "U4") (pin "1") (pinfunction "VC5_1") (pintype "passive"))
    )
    (net (code "51") (name "Net-(U4-VC6)") (class "Default")
      (node (ref "C14") (pin "2") (pinfunction "2_2") (pintype "passive"))
      (node (ref "R14") (pin "2") (pinfunction "2_2") (pintype "passive"))
      (node (ref "U4") (pin "32") (pinfunction "VC6_32") (pintype "passive"))
    )
    (net (code "52") (name "Net-(U4-VCC)") (class "Default")
      (node (ref "C25") (pin "2") (pinfunction "2_2") (pintype "passive"))
      (node (ref "C26") (pin "2") (pinfunction "2_2") (pintype "passive"))
      (node (ref "Q3") (pin "1") (pinfunction "S_1") (pintype "passive"))
      (node (ref "Q3") (pin "2") (pinfunction "S_2") (pintype "passive"))
      (node (ref "Q3") (pin "3") (pinfunction "S_3") (pintype "passive"))
      (node (ref "Q4") (pin "5") (pinfunction "D_5") (pintype "passive"))
      (node (ref "Q4") (pin "6") (pinfunction "D_6") (pintype "passive"))
      (node (ref "Q4") (pin "7") (pinfunction "D_7") (pintype "passive"))
      (node (ref "Q4") (pin "8") (pinfunction "D_8") (pintype "passive"))
      (node (ref "Q4") (pin "9") (pinfunction "D_9") (pintype "passive"))
      (node (ref "Q5") (pin "5") (pinfunction "D_5") (pintype "passive"))
      (node (ref "Q5") (pin "6") (pinfunction "D_6") (pintype "passive"))
      (node (ref "Q5") (pin "7") (pinfunction "D_7") (pintype "passive"))
      (node (ref "Q5") (pin "8") (pinfunction "D_8") (pintype "passive"))
      (node (ref "Q6") (pin "1") (pinfunction "S_1") (pintype "passive"))
      (node (ref "Q6") (pin "2") (pinfunction "S_2") (pintype "passive"))
      (node (ref "Q6") (pin "3") (pinfunction "S_3") (pintype "passive"))
      (node (ref "R27") (pin "2") (pinfunction "2_2") (pintype "passive"))
      (node (ref "R28") (pin "1") (pinfunction "1_1") (pintype "passive"))
      (node (ref "U4") (pin "24") (pinfunction "VCC_24") (pintype "passive"))
    )
    (net (code "53") (name "V+") (class "Default")
      (node (ref "D2") (pin "1") (pinfunction "A_1") (pintype "passive"))
      (node (ref "R14") (pin "1") (pinfunction "1_1") (pintype "passive"))
      (node (ref "R7") (pin "1") (pinfunction "1_1") (pintype "passive"))
      (node (ref "R8") (pin "1") (pinfunction "1_1") (pintype "passive"))
      (node (ref "U9") (pin "7") (pinfunction "7_7") (pintype "passive"))
      (node (ref "V+") (pin "1") (pinfunction "TEST_1") (pintype "passive"))
    )
    (net (code "54") (name "VSS") (class "Default")
      (node (ref "C1") (pin "1") (pinfunction "1_1") (pintype "passive"))
      (node (ref "C15") (pin "2") (pinfunction "2_2") (pintype "passive"))
      (node (ref "C16") (pin "2") (pinfunction "2_2") (pintype "passive"))
      (node (ref "C18") (pin "2") (pinfunction "2_2") (pintype "passive"))
      (node (ref "C20") (pin "2") (pinfunction "2_2") (pintype "passive"))
      (node (ref "C21") (pin "2") (pinfunction "2_2") (pintype "passive"))
      (node (ref "C22") (pin "1") (pinfunction "1_1") (pintype "passive"))
      (node (ref "C25") (pin "1") (pinfunction "1_1") (pintype "passive"))
      (node (ref "C26") (pin "1") (pinfunction "1_1") (pintype "passive"))
      (node (ref "C27") (pin "1") (pinfunction "1_1") (pintype "passive"))
      (node (ref "C4") (pin "1") (pinfunction "1_1") (pintype "passive"))
      (node (ref "C9") (pin "1") (pinfunction "1_1") (pintype "passive"))
      (node (ref "CN1") (pin "3") (pinfunction "3_3") (pintype "passive"))
      (node (ref "Q2") (pin "2") (pinfunction "S_2") (pintype "passive"))
      (node (ref "R20") (pin "2") (pinfunction "2_2") (pintype "passive"))
      (node (ref "R21") (pin "2") (pinfunction "2_2") (pintype "passive"))
      (node (ref "R24") (pin "1") (pinfunction "1_1") (pintype "passive"))
      (node (ref "U2") (pin "7") (pinfunction "VSS_7") (pintype "passive"))
      (node (ref "U4") (pin "12") (pinfunction "VC7SENSE/TS3/ADCIN1/GPIO_12") (pintype "passive"))
      (node (ref "U4") (pin "13") (pinfunction "DISP#/TS4/ADCIN2/GPIO_13") (pintype "passive"))
      (node (ref "U4") (pin "15") (pinfunction "VC7EN/DISP#/GPIO_15") (pintype "passive"))
      (node (ref "U4") (pin "20") (pinfunction "LEDCNTLA/PDSG/GPIO_20") (pintype "passive"))
      (node (ref "U4") (pin "21") (pinfunction "LEDCNTLB/GPIO_21") (pintype "passive"))
      (node (ref "U4") (pin "22") (pinfunction "LEDCNTLC/GPIO_22") (pintype "passive"))
      (node (ref "U4") (pin "9") (pinfunction "VSS_9") (pintype "passive"))
      (node (ref "U6") (pin "3") (pinfunction "3_3") (pintype "passive"))
      (node (ref "U7") (pin "2") (pinfunction "2_2") (pintype "passive"))
      (node (ref "U8") (pin "2") (pinfunction "2_2") (pintype "passive"))
      (node (ref "U9") (pin "1") (pinfunction "1_1") (pintype "passive"))
      (node (ref "VSS") (pin "1") (pinfunction "TEST_1") (pintype "passive"))
    )
    (net (code "55") (name "unconnected-(D1-Pad2)") (class "Default")
      (node (ref "D1") (pin "2") (pinfunction "2_2") (pintype "passive"))
    )
    (net (code "56") (name "unconnected-(D2-Pad2)") (class "Default")
      (node (ref "D2") (pin "2") (pinfunction "2_2") (pintype "passive"))
    )
    (net (code "57") (name "unconnected-(U1-EP-Pad9)") (class "Default")
      (node (ref "U1") (pin "9") (pinfunction "EP_9") (pintype "passive"))
    )
    (net (code "58") (name "unconnected-(U2-EP-Pad9)") (class "Default")
      (node (ref "U2") (pin "9") (pinfunction "EP_9") (pintype "passive"))
    )
    (net (code "59") (name "unconnected-(U4-EP-Pad33)") (class "Default")
      (node (ref "U4") (pin "33") (pinfunction "EP_33") (pintype "passive"))
    )
    (net (code "60") (name "unconnected-(U4-NC-Pad7)") (class "Default")
      (node (ref "U4") (pin "7") (pinfunction "NC_7") (pintype "passive"))
    )
    (net (code "61") (name "unconnected-(U4-NC-Pad14)") (class "Default")
      (node (ref "U4") (pin "14") (pinfunction "NC_14") (pintype "passive"))
    )
    (net (code "62") (name "unconnected-(U4-NC-Pad27)") (class "Default")
      (node (ref "U4") (pin "27") (pinfunction "NC_27") (pintype "passive"))
    )
    (net (code "63") (name "unconnected-(U6-Pad2)") (class "Default")
      (node (ref "U6") (pin "2") (pinfunction "2_2") (pintype "passive"))
    )
    (net (code "64") (name "unconnected-(U6-Pad4)") (class "Default")
      (node (ref "U6") (pin "4") (pinfunction "4_4") (pintype "passive"))
    )
  )
)
